# powerSwitch002.net
KiCad netlist of a schematic drawn in EAGLE
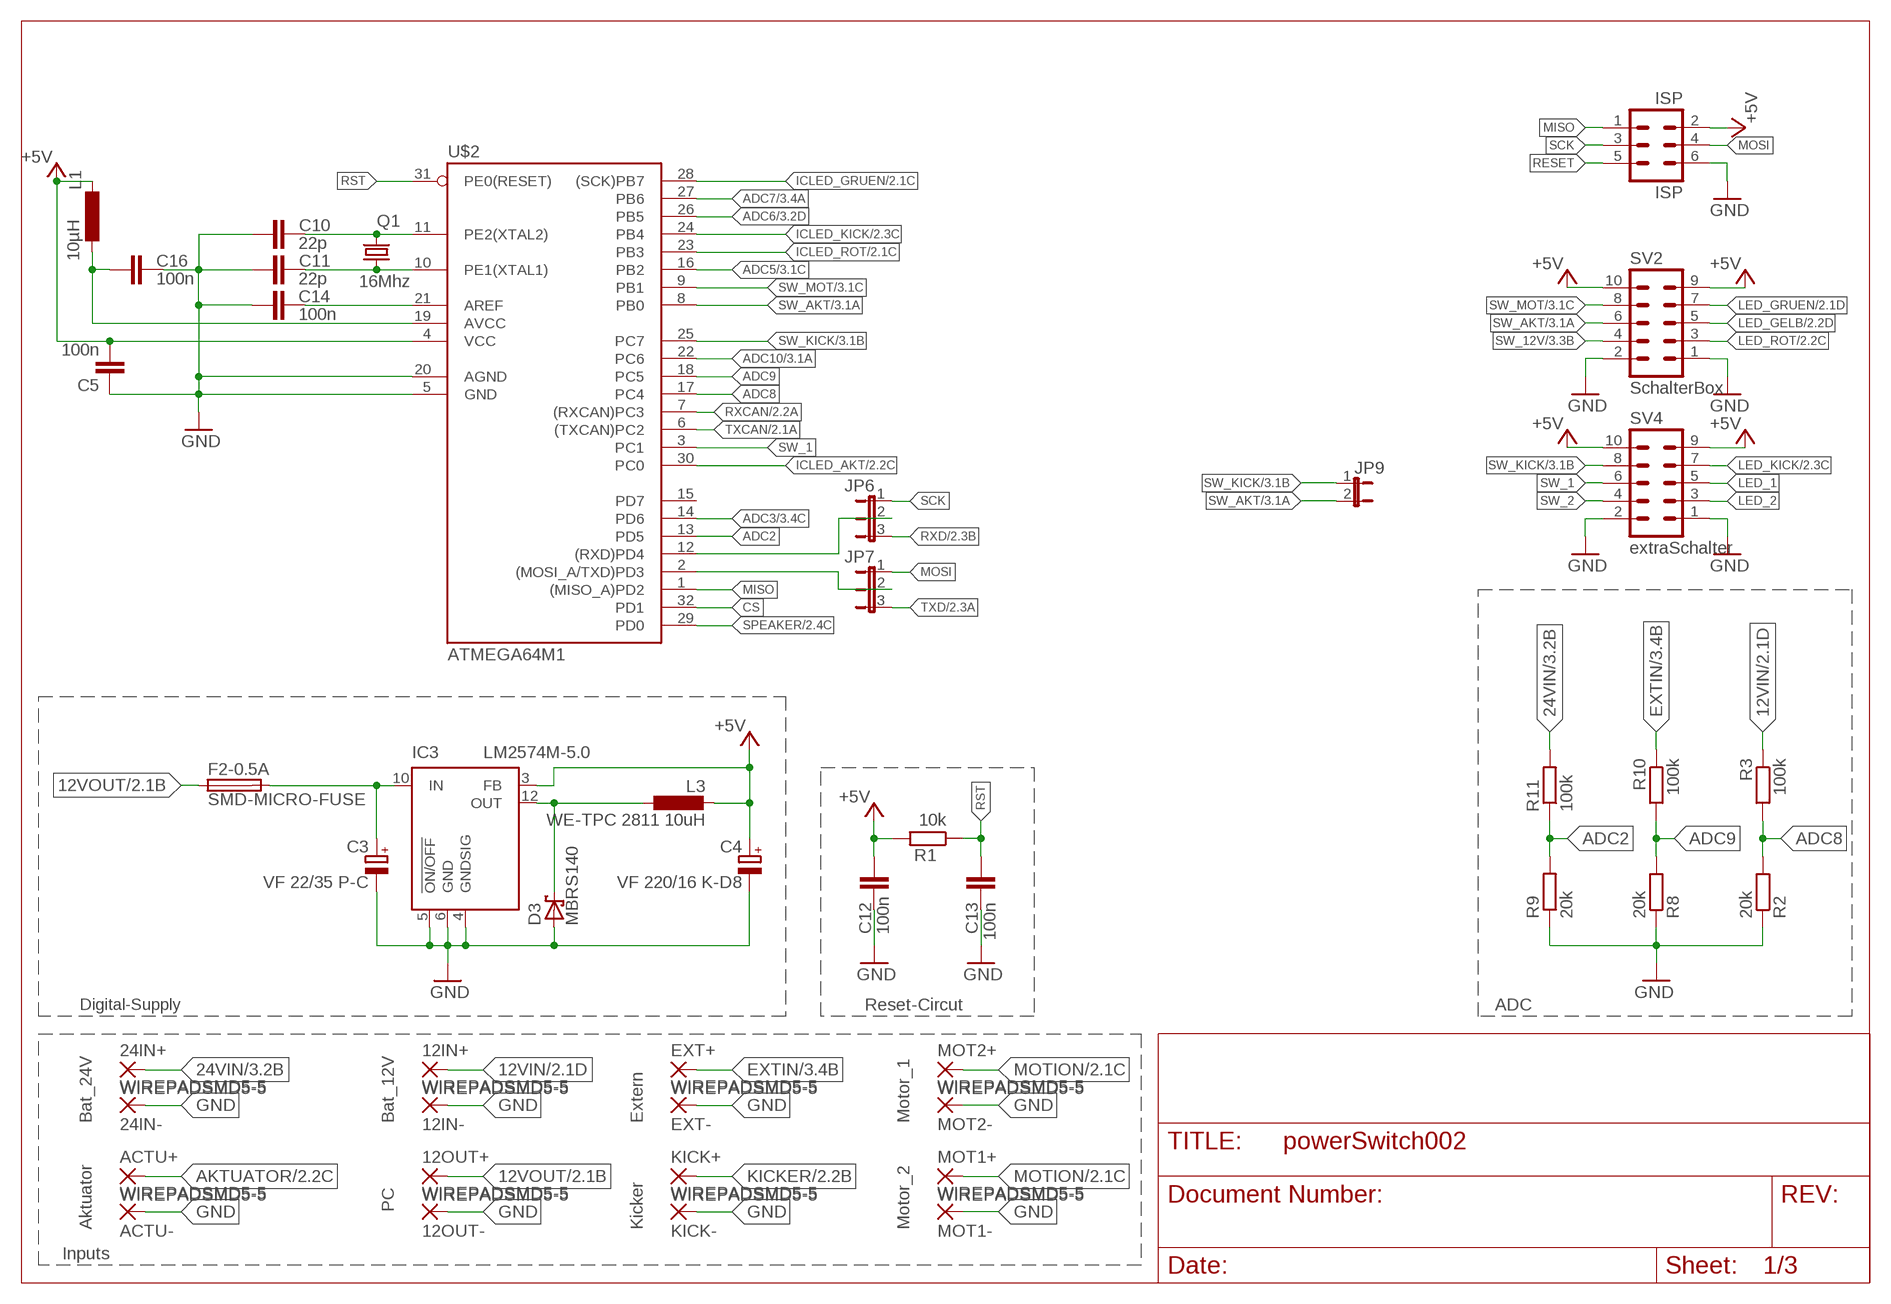
[diagram p0: schematic, sheet 1]
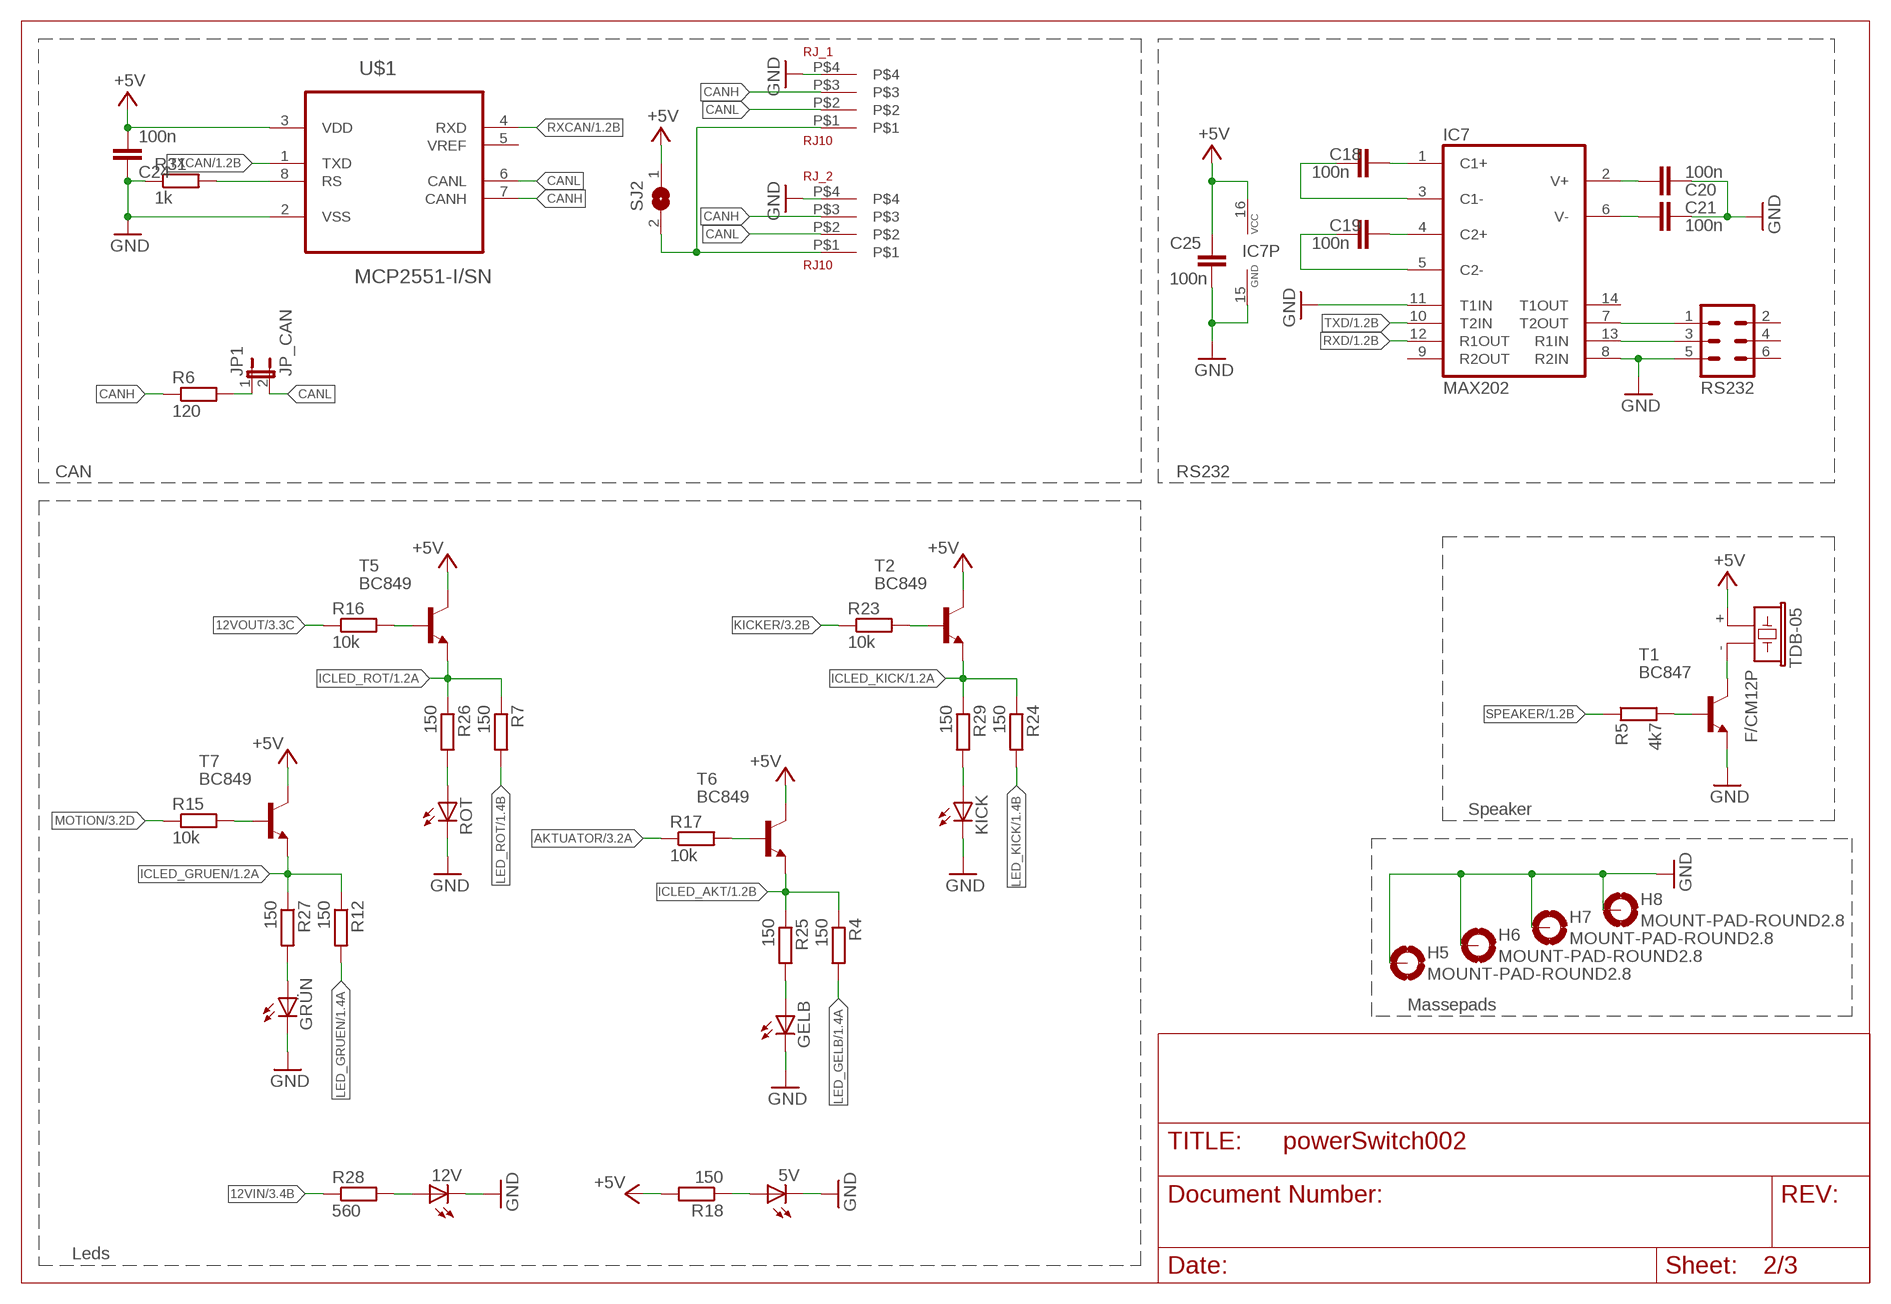
[diagram p1: schematic, sheet 2]
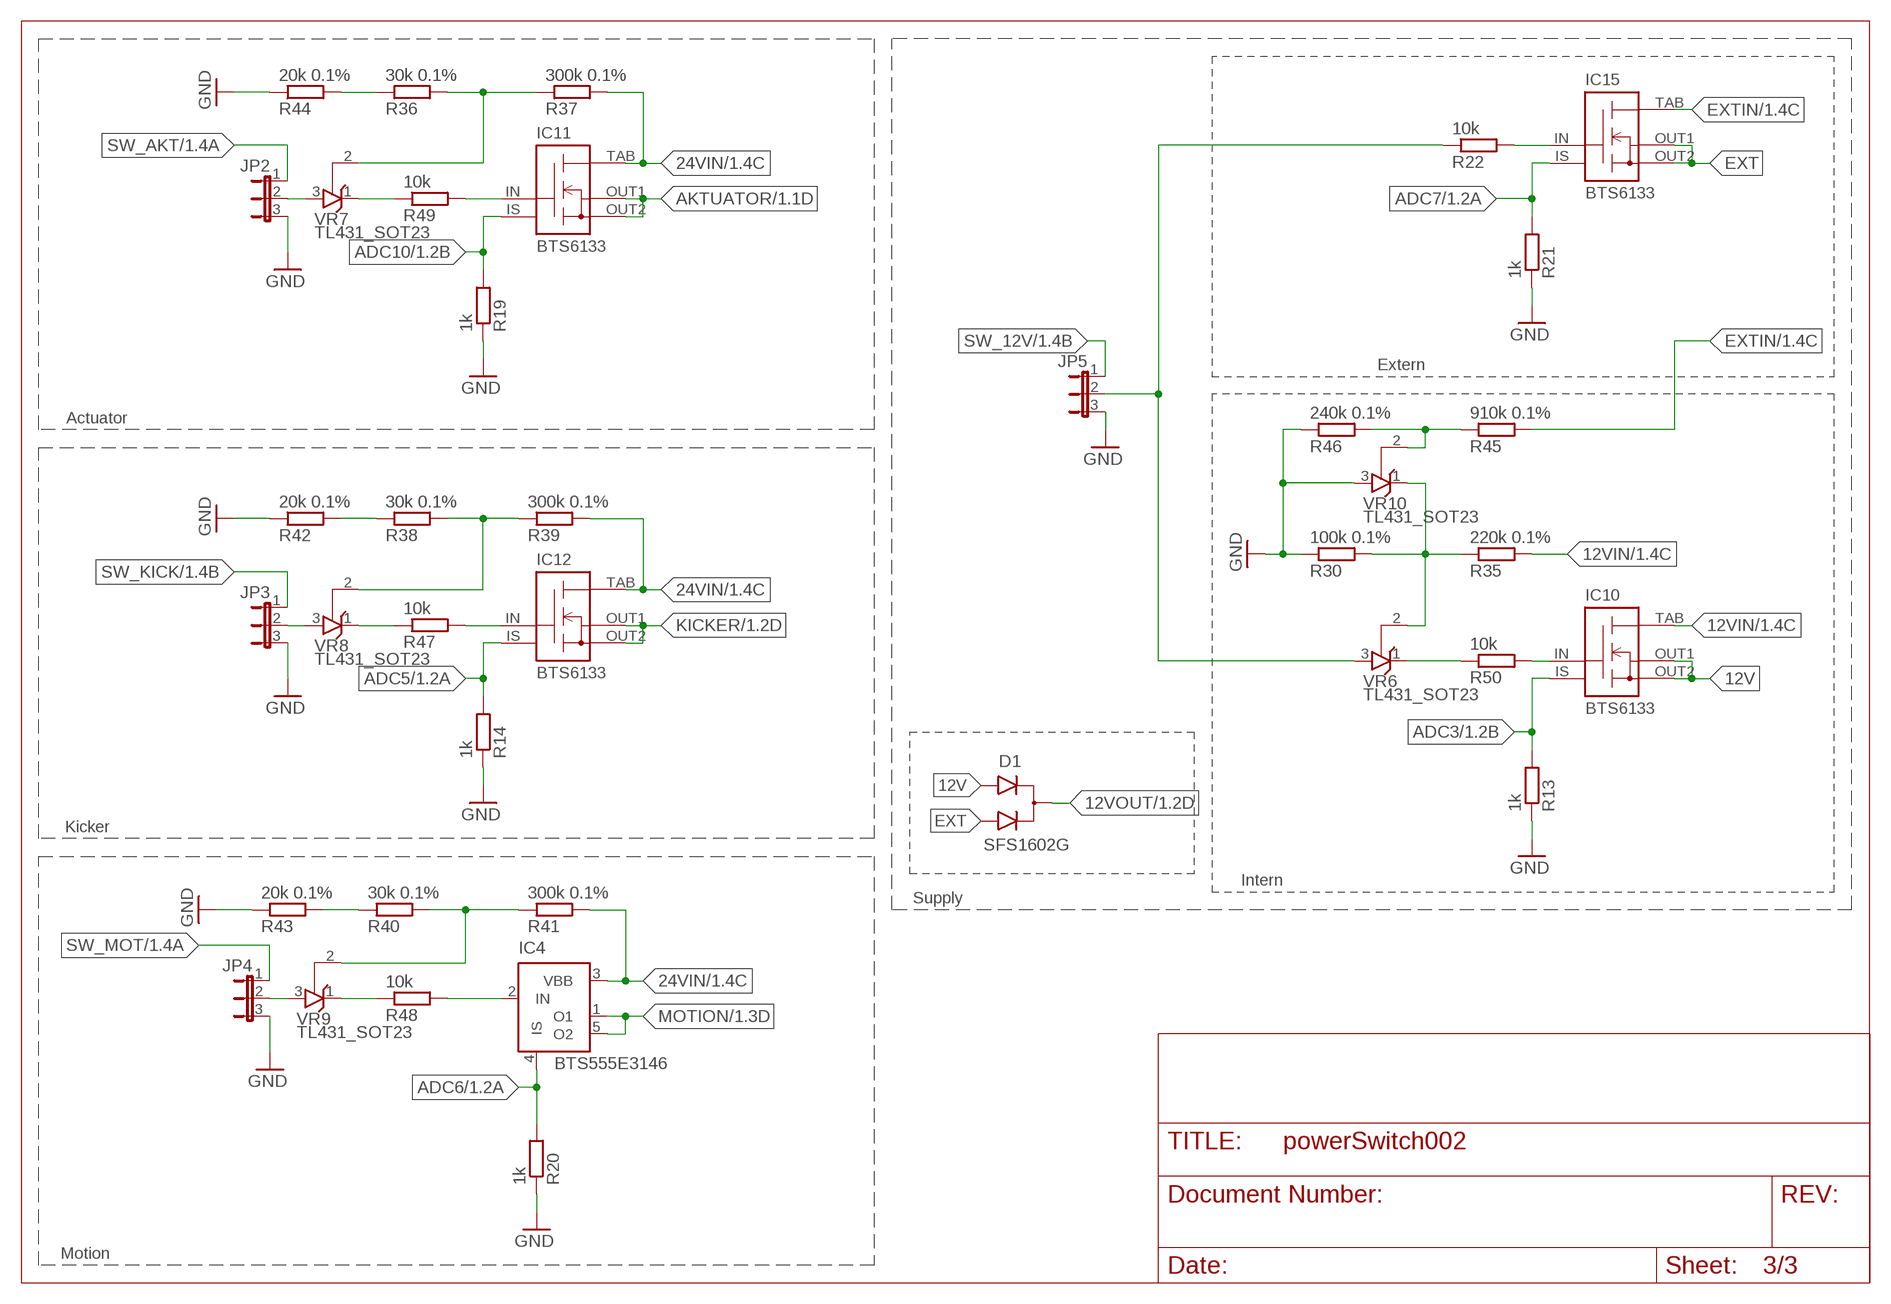
[diagram p2: schematic, sheet 3]

(export (version "E")
  (design (tool "Eeschema 10.0.6"))
  (components
    (comp (ref "12IN+")
      (value "WIREPADSMD5-5")
      (footprint "eagle-import:5-5")
      (libsource (lib "eagle-import") (part "WIREPADSMD5-5"))
    )
    (comp (ref "12IN-")
      (value "WIREPADSMD5-5")
      (footprint "eagle-import:5-5")
      (libsource (lib "eagle-import") (part "WIREPADSMD5-5"))
    )
    (comp (ref "12OUT+")
      (value "WIREPADSMD5-5")
      (footprint "eagle-import:5-5")
      (libsource (lib "eagle-import") (part "WIREPADSMD5-5"))
    )
    (comp (ref "12OUT-")
      (value "WIREPADSMD5-5")
      (footprint "eagle-import:5-5")
      (libsource (lib "eagle-import") (part "WIREPADSMD5-5"))
    )
    (comp (ref "24IN+")
      (value "WIREPADSMD5-5")
      (footprint "eagle-import:5-5")
      (libsource (lib "eagle-import") (part "WIREPADSMD5-5"))
    )
    (comp (ref "24IN-")
      (value "WIREPADSMD5-5")
      (footprint "eagle-import:5-5")
      (libsource (lib "eagle-import") (part "WIREPADSMD5-5"))
    )
    (comp (ref "ACTU+")
      (value "WIREPADSMD5-5")
      (footprint "eagle-import:5-5")
      (libsource (lib "eagle-import") (part "WIREPADSMD5-5"))
    )
    (comp (ref "ACTU-")
      (value "WIREPADSMD5-5")
      (footprint "eagle-import:5-5")
      (libsource (lib "eagle-import") (part "WIREPADSMD5-5"))
    )
    (comp (ref "C3")
      (value "VF 22/35 P-C")
      (footprint "eagle-import:PANASONIC_C")
      (libsource (lib "eagle-import") (part "CPOL-EUC"))
    )
    (comp (ref "C4")
      (value "VF 220/16 K-D8")
      (footprint "eagle-import:PANASONIC_D")
      (libsource (lib "eagle-import") (part "CPOL-EUD"))
    )
    (comp (ref "C5")
      (value "100n")
      (footprint "eagle-import:C0603K")
      (libsource (lib "eagle-import") (part "C-EUC0603K"))
    )
    (comp (ref "C10")
      (value "22p")
      (footprint "eagle-import:C0603K")
      (libsource (lib "eagle-import") (part "C-EUC0603K"))
    )
    (comp (ref "C11")
      (value "22p")
      (footprint "eagle-import:C0603K")
      (libsource (lib "eagle-import") (part "C-EUC0603K"))
    )
    (comp (ref "C12")
      (value "100n")
      (footprint "eagle-import:C0603K")
      (libsource (lib "eagle-import") (part "C-EUC0603K"))
    )
    (comp (ref "C13")
      (value "100n")
      (footprint "eagle-import:C0603K")
      (libsource (lib "eagle-import") (part "C-EUC0603K"))
    )
    (comp (ref "C14")
      (value "100n")
      (footprint "eagle-import:C0603K")
      (libsource (lib "eagle-import") (part "C-EUC0603K"))
    )
    (comp (ref "C16")
      (value "100n")
      (footprint "eagle-import:C0603K")
      (libsource (lib "eagle-import") (part "C-EUC0603K"))
    )
    (comp (ref "D3")
      (value "MBRS140")
      (footprint "eagle-import:SMB")
      (libsource (lib "eagle-import") (part "SCHOTTKY-DIODESMD"))
    )
    (comp (ref "EXT+")
      (value "WIREPADSMD5-5")
      (footprint "eagle-import:5-5")
      (libsource (lib "eagle-import") (part "WIREPADSMD5-5"))
    )
    (comp (ref "EXT-")
      (value "WIREPADSMD5-5")
      (footprint "eagle-import:5-5")
      (libsource (lib "eagle-import") (part "WIREPADSMD5-5"))
    )
    (comp (ref "F2-0.5A")
      (value "SMD-MICRO-FUSE")
      (footprint "eagle-import:SMD-6,1X2,6")
      (libsource (lib "eagle-import") (part "SMD-MICRO-FUSE"))
    )
    (comp (ref "IC3")
      (value "LM2574M-5.0")
      (footprint "eagle-import:SO14W")
      (libsource (lib "eagle-import") (part "LM2574?-M5.0"))
    )
    (comp (ref "ISP")
      (value "ISP")
      (footprint "eagle-import:ML6")
      (libsource (lib "eagle-import") (part "ML6"))
    )
    (comp (ref "JP6")
      (value "JP2E")
      (footprint "eagle-import:JP2")
      (libsource (lib "eagle-import") (part "JP2E"))
    )
    (comp (ref "JP7")
      (value "JP2E")
      (footprint "eagle-import:JP2")
      (libsource (lib "eagle-import") (part "JP2E"))
    )
    (comp (ref "JP9")
      (value "JP1E")
      (footprint "eagle-import:JP1")
      (libsource (lib "eagle-import") (part "JP1E"))
    )
    (comp (ref "KICK+")
      (value "WIREPADSMD5-5")
      (footprint "eagle-import:5-5")
      (libsource (lib "eagle-import") (part "WIREPADSMD5-5"))
    )
    (comp (ref "KICK-")
      (value "WIREPADSMD5-5")
      (footprint "eagle-import:5-5")
      (libsource (lib "eagle-import") (part "WIREPADSMD5-5"))
    )
    (comp (ref "L1")
      (value "10µH")
      (footprint "eagle-import:R0805")
      (libsource (lib "eagle-import") (part "L-EU-0805L0805"))
    )
    (comp (ref "L3")
      (value "WE-TPC 2811 10uH")
      (footprint "eagle-import:POWER-CHOKE_WE-TPC")
      (libsource (lib "eagle-import") (part "L-EUWE-TPC"))
    )
    (comp (ref "MOT1+")
      (value "WIREPADSMD5-5")
      (footprint "eagle-import:5-5")
      (libsource (lib "eagle-import") (part "WIREPADSMD5-5"))
    )
    (comp (ref "MOT1-")
      (value "WIREPADSMD5-5")
      (footprint "eagle-import:5-5")
      (libsource (lib "eagle-import") (part "WIREPADSMD5-5"))
    )
    (comp (ref "MOT2+")
      (value "WIREPADSMD5-5")
      (footprint "eagle-import:5-5")
      (libsource (lib "eagle-import") (part "WIREPADSMD5-5"))
    )
    (comp (ref "MOT2-")
      (value "WIREPADSMD5-5")
      (footprint "eagle-import:5-5")
      (libsource (lib "eagle-import") (part "WIREPADSMD5-5"))
    )
    (comp (ref "Q1")
      (value "16Mhz")
      (footprint "eagle-import:HC49U-V@1")
      (libsource (lib "eagle-import") (part "CRYTALHC49U-V"))
    )
    (comp (ref "R1")
      (value "10k")
      (footprint "eagle-import:R0805")
      (libsource (lib "eagle-import") (part "R-EU_R0805"))
    )
    (comp (ref "R2")
      (value "20k")
      (footprint "eagle-import:R0805")
      (libsource (lib "eagle-import") (part "R-EU_R0805"))
    )
    (comp (ref "R3")
      (value "100k")
      (footprint "eagle-import:R0805")
      (libsource (lib "eagle-import") (part "R-EU_R0805"))
    )
    (comp (ref "R8")
      (value "20k")
      (footprint "eagle-import:R0805")
      (libsource (lib "eagle-import") (part "R-EU_R0805"))
    )
    (comp (ref "R9")
      (value "20k")
      (footprint "eagle-import:R0805")
      (libsource (lib "eagle-import") (part "R-EU_R0805"))
    )
    (comp (ref "R10")
      (value "100k")
      (footprint "eagle-import:R0805")
      (libsource (lib "eagle-import") (part "R-EU_R0805"))
    )
    (comp (ref "R11")
      (value "100k")
      (footprint "eagle-import:R0805")
      (libsource (lib "eagle-import") (part "R-EU_R0805"))
    )
    (comp (ref "SV2")
      (value "SchalterBox")
      (footprint "eagle-import:ML10")
      (libsource (lib "eagle-import") (part "ML10"))
    )
    (comp (ref "SV4")
      (value "extraSchalter")
      (footprint "eagle-import:ML10")
      (libsource (lib "eagle-import") (part "ML10"))
    )
    (comp (ref "U$2")
      (value "ATMEGA64M1")
      (footprint "eagle-import:TQFP32-08")
      (libsource (lib "eagle-import") (part "ATMEGA64M1"))
    )
    (comp (ref "5V")
      (value "LEDCHIPLED_0805")
      (footprint "eagle-import:CHIPLED_0805")
      (libsource (lib "eagle-import") (part "LEDCHIPLED_0805"))
    )
    (comp (ref "12V")
      (value "LEDCHIPLED_0805")
      (footprint "eagle-import:CHIPLED_0805")
      (libsource (lib "eagle-import") (part "LEDCHIPLED_0805"))
    )
    (comp (ref "C18")
      (value "100n")
      (footprint "eagle-import:C0603K")
      (libsource (lib "eagle-import") (part "C-EUC0603K"))
    )
    (comp (ref "C19")
      (value "100n")
      (footprint "eagle-import:C0603K")
      (libsource (lib "eagle-import") (part "C-EUC0603K"))
    )
    (comp (ref "C20")
      (value "100n")
      (footprint "eagle-import:C0603K")
      (libsource (lib "eagle-import") (part "C-EUC0603K"))
    )
    (comp (ref "C21")
      (value "100n")
      (footprint "eagle-import:C0603K")
      (libsource (lib "eagle-import") (part "C-EUC0603K"))
    )
    (comp (ref "C24")
      (value "100n")
      (footprint "eagle-import:C0603")
      (libsource (lib "eagle-import") (part "C-EUC0603"))
    )
    (comp (ref "C25")
      (value "100n")
      (footprint "eagle-import:C0603K")
      (libsource (lib "eagle-import") (part "C-EUC0603K"))
    )
    (comp (ref "GELB")
      (value "LEDCHIPLED_0805")
      (footprint "eagle-import:CHIPLED_0805")
      (libsource (lib "eagle-import") (part "LEDCHIPLED_0805"))
    )
    (comp (ref "GRÜN")
      (value "LEDCHIPLED_0805")
      (footprint "eagle-import:CHIPLED_0805")
      (libsource (lib "eagle-import") (part "LEDCHIPLED_0805"))
    )
    (comp (ref "H5")
      (value "MOUNT-PAD-ROUND2.8")
      (footprint "eagle-import:2,8-PAD")
      (libsource (lib "eagle-import") (part "MOUNT-PAD-ROUND2.8"))
    )
    (comp (ref "H6")
      (value "MOUNT-PAD-ROUND2.8")
      (footprint "eagle-import:2,8-PAD")
      (libsource (lib "eagle-import") (part "MOUNT-PAD-ROUND2.8"))
    )
    (comp (ref "H7")
      (value "MOUNT-PAD-ROUND2.8")
      (footprint "eagle-import:2,8-PAD")
      (libsource (lib "eagle-import") (part "MOUNT-PAD-ROUND2.8"))
    )
    (comp (ref "H8")
      (value "MOUNT-PAD-ROUND2.8")
      (footprint "eagle-import:2,8-PAD")
      (libsource (lib "eagle-import") (part "MOUNT-PAD-ROUND2.8"))
    )
    (comp (ref "IC7")
      (value "MAX202")
      (footprint "eagle-import:SO16")
      (fields (field (name "MPN") "MAX3232CSE"))
      (libsource (lib "eagle-import") (part "MAX3232SEC"))
    )
    (comp (ref "JP1")
      (value "JP_CAN")
      (footprint "eagle-import:JP1")
      (libsource (lib "eagle-import") (part "JP1E"))
    )
    (comp (ref "KICK")
      (value "LEDCHIPLED_0805")
      (footprint "eagle-import:CHIPLED_0805")
      (libsource (lib "eagle-import") (part "LEDCHIPLED_0805"))
    )
    (comp (ref "R4")
      (value "150")
      (footprint "eagle-import:R0805")
      (libsource (lib "eagle-import") (part "R-EU_R0805"))
    )
    (comp (ref "R5")
      (value "4k7")
      (footprint "eagle-import:R0805")
      (libsource (lib "eagle-import") (part "R-EU_R0805"))
    )
    (comp (ref "R6")
      (value "120")
      (footprint "eagle-import:M0805")
      (libsource (lib "eagle-import") (part "R-EU_M0805"))
    )
    (comp (ref "R7")
      (value "150")
      (footprint "eagle-import:R0805")
      (libsource (lib "eagle-import") (part "R-EU_R0805"))
    )
    (comp (ref "R12")
      (value "150")
      (footprint "eagle-import:R0805")
      (libsource (lib "eagle-import") (part "R-EU_R0805"))
    )
    (comp (ref "R15")
      (value "10k")
      (footprint "eagle-import:R0805")
      (libsource (lib "eagle-import") (part "R-EU_R0805"))
    )
    (comp (ref "R16")
      (value "10k")
      (footprint "eagle-import:R0805")
      (libsource (lib "eagle-import") (part "R-EU_R0805"))
    )
    (comp (ref "R17")
      (value "10k")
      (footprint "eagle-import:R0805")
      (libsource (lib "eagle-import") (part "R-EU_R0805"))
    )
    (comp (ref "R18")
      (value "150")
      (footprint "eagle-import:R0805")
      (libsource (lib "eagle-import") (part "R-EU_R0805"))
    )
    (comp (ref "R23")
      (value "10k")
      (footprint "eagle-import:R0805")
      (libsource (lib "eagle-import") (part "R-EU_R0805"))
    )
    (comp (ref "R24")
      (value "150")
      (footprint "eagle-import:R0805")
      (libsource (lib "eagle-import") (part "R-EU_R0805"))
    )
    (comp (ref "R25")
      (value "150")
      (footprint "eagle-import:R0805")
      (libsource (lib "eagle-import") (part "R-EU_R0805"))
    )
    (comp (ref "R26")
      (value "150")
      (footprint "eagle-import:R0805")
      (libsource (lib "eagle-import") (part "R-EU_R0805"))
    )
    (comp (ref "R27")
      (value "150")
      (footprint "eagle-import:R0805")
      (libsource (lib "eagle-import") (part "R-EU_R0805"))
    )
    (comp (ref "R28")
      (value "560")
      (footprint "eagle-import:R0805")
      (libsource (lib "eagle-import") (part "R-EU_R0805"))
    )
    (comp (ref "R29")
      (value "150")
      (footprint "eagle-import:R0805")
      (libsource (lib "eagle-import") (part "R-EU_R0805"))
    )
    (comp (ref "R31")
      (value "1k")
      (footprint "eagle-import:R0805")
      (libsource (lib "eagle-import") (part "R-EU_R0805"))
    )
    (comp (ref "RJ_1")
      (value "RJ10")
      (footprint "eagle-import:RJ10")
      (libsource (lib "eagle-import") (part "RJ10"))
    )
    (comp (ref "RJ_2")
      (value "RJ10")
      (footprint "eagle-import:RJ10")
      (libsource (lib "eagle-import") (part "RJ10"))
    )
    (comp (ref "ROT")
      (value "LEDCHIPLED_0805")
      (footprint "eagle-import:CHIPLED_0805")
      (libsource (lib "eagle-import") (part "LEDCHIPLED_0805"))
    )
    (comp (ref "RS232")
      (value "ML6")
      (footprint "eagle-import:ML6")
      (libsource (lib "eagle-import") (part "ML6"))
    )
    (comp (ref "SJ2") (value "SJ") (footprint "eagle-import:SJ") (libsource (lib "eagle-import") (part "SJ")))
    (comp (ref "T1")
      (value "BC847")
      (footprint "eagle-import:SOT23")
      (libsource (lib "eagle-import") (part "BC847"))
    )
    (comp (ref "T2")
      (value "BC849")
      (footprint "eagle-import:SOT23")
      (libsource (lib "eagle-import") (part "BC849"))
    )
    (comp (ref "T5")
      (value "BC849")
      (footprint "eagle-import:SOT23")
      (libsource (lib "eagle-import") (part "BC849"))
    )
    (comp (ref "T6")
      (value "BC849")
      (footprint "eagle-import:SOT23")
      (libsource (lib "eagle-import") (part "BC849"))
    )
    (comp (ref "T7")
      (value "BC849")
      (footprint "eagle-import:SOT23")
      (libsource (lib "eagle-import") (part "BC849"))
    )
    (comp (ref "TDB-05")
      (value "F/CM12P")
      (footprint "eagle-import:F_CM12P")
      (libsource (lib "eagle-import") (part "F/CM12P"))
    )
    (comp (ref "U$1")
      (value "MCP2551-I/SN")
      (footprint "eagle-import:SOIC127P600X175-8N")
      (libsource (lib "eagle-import") (part "MCP2551-I/SN"))
    )
    (comp (ref "D1")
      (value "SFS1602G")
      (footprint "eagle-import:D2PAK")
      (libsource (lib "eagle-import") (part "SFS160G"))
    )
    (comp (ref "IC4")
      (value "BTS555E3146")
      (footprint "eagle-import:TO220-52")
      (libsource (lib "eagle-import") (part "BTS555E3146"))
    )
    (comp (ref "IC10")
      (value "BTS6133")
      (footprint "eagle-import:TO252-51")
      (libsource (lib "eagle-import") (part "BTS6133"))
    )
    (comp (ref "IC11")
      (value "BTS6133")
      (footprint "eagle-import:TO252-51")
      (libsource (lib "eagle-import") (part "BTS6133"))
    )
    (comp (ref "IC12")
      (value "BTS6133")
      (footprint "eagle-import:TO252-51")
      (libsource (lib "eagle-import") (part "BTS6133"))
    )
    (comp (ref "IC15")
      (value "BTS6133")
      (footprint "eagle-import:TO252-51")
      (libsource (lib "eagle-import") (part "BTS6133"))
    )
    (comp (ref "JP2")
      (value "JP2E")
      (footprint "eagle-import:JP2")
      (libsource (lib "eagle-import") (part "JP2E"))
    )
    (comp (ref "JP3")
      (value "JP2E")
      (footprint "eagle-import:JP2")
      (libsource (lib "eagle-import") (part "JP2E"))
    )
    (comp (ref "JP4")
      (value "JP2E")
      (footprint "eagle-import:JP2")
      (libsource (lib "eagle-import") (part "JP2E"))
    )
    (comp (ref "JP5")
      (value "JP2E")
      (footprint "eagle-import:JP2")
      (libsource (lib "eagle-import") (part "JP2E"))
    )
    (comp (ref "R13")
      (value "1k")
      (footprint "eagle-import:R0805")
      (libsource (lib "eagle-import") (part "R-EU_R0805"))
    )
    (comp (ref "R14")
      (value "1k")
      (footprint "eagle-import:R0805")
      (libsource (lib "eagle-import") (part "R-EU_R0805"))
    )
    (comp (ref "R19")
      (value "1k")
      (footprint "eagle-import:R0805")
      (libsource (lib "eagle-import") (part "R-EU_R0805"))
    )
    (comp (ref "R20")
      (value "1k")
      (footprint "eagle-import:R0805")
      (libsource (lib "eagle-import") (part "R-EU_R0805"))
    )
    (comp (ref "R21")
      (value "1k")
      (footprint "eagle-import:R0805")
      (libsource (lib "eagle-import") (part "R-EU_R0805"))
    )
    (comp (ref "R22")
      (value "10k")
      (footprint "eagle-import:R0805")
      (libsource (lib "eagle-import") (part "R-EU_R0805"))
    )
    (comp (ref "R30")
      (value "100k 0.1%")
      (footprint "eagle-import:R0805")
      (libsource (lib "eagle-import") (part "R-EU_R0805"))
    )
    (comp (ref "R35")
      (value "220k 0.1%")
      (footprint "eagle-import:R0805")
      (libsource (lib "eagle-import") (part "R-EU_R0805"))
    )
    (comp (ref "R36")
      (value "30k 0.1%")
      (footprint "eagle-import:R0805")
      (libsource (lib "eagle-import") (part "R-EU_R0805"))
    )
    (comp (ref "R37")
      (value "300k 0.1%")
      (footprint "eagle-import:R0805")
      (libsource (lib "eagle-import") (part "R-EU_R0805"))
    )
    (comp (ref "R38")
      (value "30k 0.1%")
      (footprint "eagle-import:R0805")
      (libsource (lib "eagle-import") (part "R-EU_R0805"))
    )
    (comp (ref "R39")
      (value "300k 0.1%")
      (footprint "eagle-import:R0805")
      (libsource (lib "eagle-import") (part "R-EU_R0805"))
    )
    (comp (ref "R40")
      (value "30k 0.1%")
      (footprint "eagle-import:R0805")
      (libsource (lib "eagle-import") (part "R-EU_R0805"))
    )
    (comp (ref "R41")
      (value "300k 0.1%")
      (footprint "eagle-import:R0805")
      (libsource (lib "eagle-import") (part "R-EU_R0805"))
    )
    (comp (ref "R42")
      (value "20k 0.1%")
      (footprint "eagle-import:R0805")
      (libsource (lib "eagle-import") (part "R-EU_R0805"))
    )
    (comp (ref "R43")
      (value "20k 0.1%")
      (footprint "eagle-import:R0805")
      (libsource (lib "eagle-import") (part "R-EU_R0805"))
    )
    (comp (ref "R44")
      (value "20k 0.1%")
      (footprint "eagle-import:R0805")
      (libsource (lib "eagle-import") (part "R-EU_R0805"))
    )
    (comp (ref "R45")
      (value "910k 0.1%")
      (footprint "eagle-import:R0805")
      (libsource (lib "eagle-import") (part "R-EU_R0805"))
    )
    (comp (ref "R46")
      (value "240k 0.1%")
      (footprint "eagle-import:R0805")
      (libsource (lib "eagle-import") (part "R-EU_R0805"))
    )
    (comp (ref "R47")
      (value "10k")
      (footprint "eagle-import:R0805")
      (libsource (lib "eagle-import") (part "R-EU_R0805"))
    )
    (comp (ref "R48")
      (value "10k")
      (footprint "eagle-import:R0805")
      (libsource (lib "eagle-import") (part "R-EU_R0805"))
    )
    (comp (ref "R49")
      (value "10k")
      (footprint "eagle-import:R0805")
      (libsource (lib "eagle-import") (part "R-EU_R0805"))
    )
    (comp (ref "R50")
      (value "10k")
      (footprint "eagle-import:R0805")
      (libsource (lib "eagle-import") (part "R-EU_R0805"))
    )
    (comp (ref "VR6")
      (value "TL431_SOT23")
      (footprint "eagle-import:SOT23")
      (libsource (lib "eagle-import") (part "TL431_SOT23"))
    )
    (comp (ref "VR7")
      (value "TL431_SOT23")
      (footprint "eagle-import:SOT23")
      (libsource (lib "eagle-import") (part "TL431_SOT23"))
    )
    (comp (ref "VR8")
      (value "TL431_SOT23")
      (footprint "eagle-import:SOT23")
      (libsource (lib "eagle-import") (part "TL431_SOT23"))
    )
    (comp (ref "VR9")
      (value "TL431_SOT23")
      (footprint "eagle-import:SOT23")
      (libsource (lib "eagle-import") (part "TL431_SOT23"))
    )
    (comp (ref "VR10")
      (value "TL431_SOT23")
      (footprint "eagle-import:SOT23")
      (libsource (lib "eagle-import") (part "TL431_SOT23"))
    )
  )
  (nets
    (net (code "1") (name "+5V") (class "Default")
      (node (ref "C12") (pin "2") (pinfunction "2_2") (pintype "passive"))
      (node (ref "C24") (pin "2") (pinfunction "2_2") (pintype "passive"))
      (node (ref "C25") (pin "1") (pinfunction "1_1") (pintype "passive"))
      (node (ref "C4") (pin "+") (pinfunction "+_+") (pintype "passive"))
      (node (ref "C5") (pin "2") (pinfunction "2_2") (pintype "passive"))
      (node (ref "IC3") (pin "3") (pinfunction "FB_3") (pintype "input"))
      (node (ref "IC7") (pin "16") (pinfunction "VCC_16") (pintype "power_in"))
      (node (ref "ISP") (pin "2") (pinfunction "2_2") (pintype "passive"))
      (node (ref "L1") (pin "2") (pinfunction "2_2") (pintype "passive"))
      (node (ref "L3") (pin "2") (pinfunction "2_2") (pintype "passive"))
      (node (ref "R1") (pin "2") (pinfunction "2_2") (pintype "passive"))
      (node (ref "R18") (pin "2") (pinfunction "2_2") (pintype "passive"))
      (node (ref "SJ2") (pin "1") (pinfunction "1_1") (pintype "passive"))
      (node (ref "SV2") (pin "10") (pinfunction "10_10") (pintype "passive"))
      (node (ref "SV2") (pin "9") (pinfunction "9_9") (pintype "passive"))
      (node (ref "SV4") (pin "10") (pinfunction "10_10") (pintype "passive"))
      (node (ref "SV4") (pin "9") (pinfunction "9_9") (pintype "passive"))
      (node (ref "T2") (pin "3") (pinfunction "C_3") (pintype "passive"))
      (node (ref "T5") (pin "3") (pinfunction "C_3") (pintype "passive"))
      (node (ref "T6") (pin "3") (pinfunction "C_3") (pintype "passive"))
      (node (ref "T7") (pin "3") (pinfunction "C_3") (pintype "passive"))
      (node (ref "TDB-05") (pin "+") (pinfunction "1_+") (pintype "passive"))
      (node (ref "U$1") (pin "3") (pinfunction "VDD_3") (pintype "power_in"))
      (node (ref "U$2") (pin "4") (pinfunction "VCC_4") (pintype "bidirectional"))
    )
    (net (code "2") (name "12V") (class "Default")
      (node (ref "D1") (pin "P$1") (pinfunction "P$1_P$1") (pintype "bidirectional"))
      (node (ref "IC10") (pin "OUT1") (pinfunction "OUT_OUT1") (pintype "passive"))
      (node (ref "IC10") (pin "OUT2") (pinfunction "OUT_OUT2") (pintype "passive"))
    )
    (net (code "3") (name "12VIN") (class "Default")
      (node (ref "12IN+") (pin "P$1") (pinfunction "P_P$1") (pintype "passive"))
      (node (ref "IC10") (pin "TAB") (pinfunction "VBB_TAB") (pintype "power_in"))
      (node (ref "R28") (pin "1") (pinfunction "1_1") (pintype "passive"))
      (node (ref "R3") (pin "1") (pinfunction "1_1") (pintype "passive"))
      (node (ref "R35") (pin "2") (pinfunction "2_2") (pintype "passive"))
    )
    (net (code "4") (name "12VOUT") (class "Default")
      (node (ref "12OUT+") (pin "P$1") (pinfunction "P_P$1") (pintype "passive"))
      (node (ref "D1") (pin "P$3") (pinfunction "P$3_P$3") (pintype "bidirectional"))
      (node (ref "F2-0.5A") (pin "1") (pinfunction "1_1") (pintype "passive"))
      (node (ref "R16") (pin "1") (pinfunction "1_1") (pintype "passive"))
    )
    (net (code "5") (name "24VIN") (class "Default")
      (node (ref "24IN+") (pin "P$1") (pinfunction "P_P$1") (pintype "passive"))
      (node (ref "IC11") (pin "TAB") (pinfunction "VBB_TAB") (pintype "power_in"))
      (node (ref "IC12") (pin "TAB") (pinfunction "VBB_TAB") (pintype "power_in"))
      (node (ref "IC4") (pin "3") (pinfunction "VBB_3") (pintype "passive"))
      (node (ref "R11") (pin "2") (pinfunction "2_2") (pintype "passive"))
      (node (ref "R37") (pin "2") (pinfunction "2_2") (pintype "passive"))
      (node (ref "R39") (pin "2") (pinfunction "2_2") (pintype "passive"))
      (node (ref "R41") (pin "2") (pinfunction "2_2") (pintype "passive"))
    )
    (net (code "6") (name "ADC2") (class "Default")
      (node (ref "R11") (pin "1") (pinfunction "1_1") (pintype "passive"))
      (node (ref "R9") (pin "2") (pinfunction "2_2") (pintype "passive"))
      (node (ref "U$2") (pin "13") (pinfunction "PD5_13") (pintype "bidirectional"))
    )
    (net (code "7") (name "ADC3") (class "Default")
      (node (ref "IC10") (pin "IS") (pinfunction "IS_IS") (pintype "passive"))
      (node (ref "R13") (pin "2") (pinfunction "2_2") (pintype "passive"))
      (node (ref "U$2") (pin "14") (pinfunction "PD6_14") (pintype "bidirectional"))
    )
    (net (code "8") (name "ADC5") (class "Default")
      (node (ref "IC12") (pin "IS") (pinfunction "IS_IS") (pintype "passive"))
      (node (ref "R14") (pin "2") (pinfunction "2_2") (pintype "passive"))
      (node (ref "U$2") (pin "16") (pinfunction "PB2_16") (pintype "bidirectional"))
    )
    (net (code "9") (name "ADC6") (class "Default")
      (node (ref "IC4") (pin "4") (pinfunction "IS_4") (pintype "passive"))
      (node (ref "R20") (pin "2") (pinfunction "2_2") (pintype "passive"))
      (node (ref "U$2") (pin "26") (pinfunction "PB5_26") (pintype "bidirectional"))
    )
    (net (code "10") (name "ADC7") (class "Default")
      (node (ref "IC15") (pin "IS") (pinfunction "IS_IS") (pintype "passive"))
      (node (ref "R21") (pin "2") (pinfunction "2_2") (pintype "passive"))
      (node (ref "U$2") (pin "27") (pinfunction "PB6_27") (pintype "bidirectional"))
    )
    (net (code "11") (name "ADC8") (class "Default")
      (node (ref "R2") (pin "2") (pinfunction "2_2") (pintype "passive"))
      (node (ref "R3") (pin "2") (pinfunction "2_2") (pintype "passive"))
      (node (ref "U$2") (pin "17") (pinfunction "PC4_17") (pintype "bidirectional"))
    )
    (net (code "12") (name "ADC9") (class "Default")
      (node (ref "R10") (pin "2") (pinfunction "2_2") (pintype "passive"))
      (node (ref "R8") (pin "2") (pinfunction "2_2") (pintype "passive"))
      (node (ref "U$2") (pin "18") (pinfunction "PC5_18") (pintype "bidirectional"))
    )
    (net (code "13") (name "ADC10") (class "Default")
      (node (ref "IC11") (pin "IS") (pinfunction "IS_IS") (pintype "passive"))
      (node (ref "R19") (pin "2") (pinfunction "2_2") (pintype "passive"))
      (node (ref "U$2") (pin "22") (pinfunction "PC6_22") (pintype "bidirectional"))
    )
    (net (code "14") (name "AKTUATOR") (class "Default")
      (node (ref "ACTU+") (pin "P$1") (pinfunction "P_P$1") (pintype "passive"))
      (node (ref "IC11") (pin "OUT1") (pinfunction "OUT_OUT1") (pintype "passive"))
      (node (ref "IC11") (pin "OUT2") (pinfunction "OUT_OUT2") (pintype "passive"))
      (node (ref "R17") (pin "1") (pinfunction "1_1") (pintype "passive"))
    )
    (net (code "15") (name "CANH") (class "Default")
      (node (ref "R6") (pin "1") (pinfunction "1_1") (pintype "passive"))
      (node (ref "RJ_1") (pin "P$3") (pinfunction "P$3_P$3") (pintype "bidirectional"))
      (node (ref "RJ_2") (pin "P$3") (pinfunction "P$3_P$3") (pintype "bidirectional"))
      (node (ref "U$1") (pin "7") (pinfunction "CANH_7") (pintype "bidirectional"))
    )
    (net (code "16") (name "CANL") (class "Default")
      (node (ref "JP1") (pin "2") (pinfunction "2_2") (pintype "passive"))
      (node (ref "RJ_1") (pin "P$2") (pinfunction "P$2_P$2") (pintype "bidirectional"))
      (node (ref "RJ_2") (pin "P$2") (pinfunction "P$2_P$2") (pintype "bidirectional"))
      (node (ref "U$1") (pin "6") (pinfunction "CANL_6") (pintype "bidirectional"))
    )
    (net (code "17") (name "CS") (class "Default")
      (node (ref "U$2") (pin "32") (pinfunction "PD1_32") (pintype "bidirectional"))
    )
    (net (code "18") (name "EXT") (class "Default")
      (node (ref "D1") (pin "P$2") (pinfunction "P$2_P$2") (pintype "bidirectional"))
      (node (ref "IC15") (pin "OUT1") (pinfunction "OUT_OUT1") (pintype "passive"))
      (node (ref "IC15") (pin "OUT2") (pinfunction "OUT_OUT2") (pintype "passive"))
    )
    (net (code "19") (name "EXTIN") (class "Default")
      (node (ref "EXT+") (pin "P$1") (pinfunction "P_P$1") (pintype "passive"))
      (node (ref "IC15") (pin "TAB") (pinfunction "VBB_TAB") (pintype "power_in"))
      (node (ref "R10") (pin "1") (pinfunction "1_1") (pintype "passive"))
      (node (ref "R45") (pin "2") (pinfunction "2_2") (pintype "passive"))
    )
    (net (code "20") (name "GND") (class "Default")
      (node (ref "12IN-") (pin "P$1") (pinfunction "P_P$1") (pintype "passive"))
      (node (ref "12OUT-") (pin "P$1") (pinfunction "P_P$1") (pintype "passive"))
      (node (ref "12V") (pin "C") (pinfunction "C_C") (pintype "passive"))
      (node (ref "24IN-") (pin "P$1") (pinfunction "P_P$1") (pintype "passive"))
      (node (ref "5V") (pin "C") (pinfunction "C_C") (pintype "passive"))
      (node (ref "ACTU-") (pin "P$1") (pinfunction "P_P$1") (pintype "passive"))
      (node (ref "C10") (pin "1") (pinfunction "1_1") (pintype "passive"))
      (node (ref "C11") (pin "1") (pinfunction "1_1") (pintype "passive"))
      (node (ref "C12") (pin "1") (pinfunction "1_1") (pintype "passive"))
      (node (ref "C13") (pin "1") (pinfunction "1_1") (pintype "passive"))
      (node (ref "C14") (pin "1") (pinfunction "1_1") (pintype "passive"))
      (node (ref "C16") (pin "2") (pinfunction "2_2") (pintype "passive"))
      (node (ref "C20") (pin "2") (pinfunction "2_2") (pintype "passive"))
      (node (ref "C21") (pin "2") (pinfunction "2_2") (pintype "passive"))
      (node (ref "C24") (pin "1") (pinfunction "1_1") (pintype "passive"))
      (node (ref "C25") (pin "2") (pinfunction "2_2") (pintype "passive"))
      (node (ref "C3") (pin "-") (pinfunction "-_-") (pintype "passive"))
      (node (ref "C4") (pin "-") (pinfunction "-_-") (pintype "passive"))
      (node (ref "C5") (pin "1") (pinfunction "1_1") (pintype "passive"))
      (node (ref "D3") (pin "A") (pinfunction "A_A") (pintype "passive"))
      (node (ref "EXT-") (pin "P$1") (pinfunction "P_P$1") (pintype "passive"))
      (node (ref "GELB") (pin "C") (pinfunction "C_C") (pintype "passive"))
      (node (ref "GRÜN") (pin "C") (pinfunction "C_C") (pintype "passive"))
      (node (ref "H5") (pin "B2,8") (pinfunction "MOUNT_B2,8") (pintype "passive"))
      (node (ref "H6") (pin "B2,8") (pinfunction "MOUNT_B2,8") (pintype "passive"))
      (node (ref "H7") (pin "B2,8") (pinfunction "MOUNT_B2,8") (pintype "passive"))
      (node (ref "H8") (pin "B2,8") (pinfunction "MOUNT_B2,8") (pintype "passive"))
      (node (ref "IC3") (pin "4") (pinfunction "GNDSIG_4") (pintype "input"))
      (node (ref "IC3") (pin "5") (pinfunction "~{ON/OFF}_5") (pintype "input"))
      (node (ref "IC3") (pin "6") (pinfunction "GND_6") (pintype "power_in"))
      (node (ref "IC7") (pin "11") (pinfunction "T1IN_11") (pintype "input"))
      (node (ref "IC7") (pin "15") (pinfunction "GND_15") (pintype "power_in"))
      (node (ref "IC7") (pin "8") (pinfunction "R2IN_8") (pintype "input"))
      (node (ref "ISP") (pin "6") (pinfunction "6_6") (pintype "passive"))
      (node (ref "JP2") (pin "3") (pinfunction "3_3") (pintype "passive"))
      (node (ref "JP3") (pin "3") (pinfunction "3_3") (pintype "passive"))
      (node (ref "JP4") (pin "3") (pinfunction "3_3") (pintype "passive"))
      (node (ref "JP5") (pin "3") (pinfunction "3_3") (pintype "passive"))
      (node (ref "KICK") (pin "C") (pinfunction "C_C") (pintype "passive"))
      (node (ref "KICK-") (pin "P$1") (pinfunction "P_P$1") (pintype "passive"))
      (node (ref "MOT1-") (pin "P$1") (pinfunction "P_P$1") (pintype "passive"))
      (node (ref "MOT2-") (pin "P$1") (pinfunction "P_P$1") (pintype "passive"))
      (node (ref "R13") (pin "1") (pinfunction "1_1") (pintype "passive"))
      (node (ref "R14") (pin "1") (pinfunction "1_1") (pintype "passive"))
      (node (ref "R19") (pin "1") (pinfunction "1_1") (pintype "passive"))
      (node (ref "R2") (pin "1") (pinfunction "1_1") (pintype "passive"))
      (node (ref "R20") (pin "1") (pinfunction "1_1") (pintype "passive"))
      (node (ref "R21") (pin "1") (pinfunction "1_1") (pintype "passive"))
      (node (ref "R30") (pin "1") (pinfunction "1_1") (pintype "passive"))
      (node (ref "R31") (pin "1") (pinfunction "1_1") (pintype "passive"))
      (node (ref "R42") (pin "1") (pinfunction "1_1") (pintype "passive"))
      (node (ref "R43") (pin "1") (pinfunction "1_1") (pintype "passive"))
      (node (ref "R44") (pin "1") (pinfunction "1_1") (pintype "passive"))
      (node (ref "R46") (pin "1") (pinfunction "1_1") (pintype "passive"))
      (node (ref "R8") (pin "1") (pinfunction "1_1") (pintype "passive"))
      (node (ref "R9") (pin "1") (pinfunction "1_1") (pintype "passive"))
      (node (ref "RJ_1") (pin "P$4") (pinfunction "P$4_P$4") (pintype "bidirectional"))
      (node (ref "RJ_2") (pin "P$4") (pinfunction "P$4_P$4") (pintype "bidirectional"))
      (node (ref "ROT") (pin "C") (pinfunction "C_C") (pintype "passive"))
      (node (ref "RS232") (pin "5") (pinfunction "5_5") (pintype "passive"))
      (node (ref "SV2") (pin "1") (pinfunction "1_1") (pintype "passive"))
      (node (ref "SV2") (pin "2") (pinfunction "2_2") (pintype "passive"))
      (node (ref "SV4") (pin "1") (pinfunction "1_1") (pintype "passive"))
      (node (ref "SV4") (pin "2") (pinfunction "2_2") (pintype "passive"))
      (node (ref "T1") (pin "2") (pinfunction "E_2") (pintype "passive"))
      (node (ref "U$1") (pin "2") (pinfunction "VSS_2") (pintype "passive"))
      (node (ref "U$2") (pin "20") (pinfunction "AGND_20") (pintype "power_in"))
      (node (ref "U$2") (pin "5") (pinfunction "GND_5") (pintype "power_in"))
      (node (ref "VR10") (pin "3") (pinfunction "A_3") (pintype "passive"))
    )
    (net (code "21") (name "ICLED_AKT") (class "Default")
      (node (ref "R25") (pin "1") (pinfunction "1_1") (pintype "passive"))
      (node (ref "R4") (pin "1") (pinfunction "1_1") (pintype "passive"))
      (node (ref "T6") (pin "2") (pinfunction "E_2") (pintype "passive"))
      (node (ref "U$2") (pin "30") (pinfunction "PC0_30") (pintype "bidirectional"))
    )
    (net (code "22") (name "ICLED_GRUEN") (class "Default")
      (node (ref "R12") (pin "1") (pinfunction "1_1") (pintype "passive"))
      (node (ref "R27") (pin "1") (pinfunction "1_1") (pintype "passive"))
      (node (ref "T7") (pin "2") (pinfunction "E_2") (pintype "passive"))
      (node (ref "U$2") (pin "28") (pinfunction "(SCK)PB7_28") (pintype "bidirectional"))
    )
    (net (code "23") (name "ICLED_KICK") (class "Default")
      (node (ref "R24") (pin "1") (pinfunction "1_1") (pintype "passive"))
      (node (ref "R29") (pin "1") (pinfunction "1_1") (pintype "passive"))
      (node (ref "T2") (pin "2") (pinfunction "E_2") (pintype "passive"))
      (node (ref "U$2") (pin "24") (pinfunction "PB4_24") (pintype "bidirectional"))
    )
    (net (code "24") (name "ICLED_ROT") (class "Default")
      (node (ref "R26") (pin "1") (pinfunction "1_1") (pintype "passive"))
      (node (ref "R7") (pin "1") (pinfunction "1_1") (pintype "passive"))
      (node (ref "T5") (pin "2") (pinfunction "E_2") (pintype "passive"))
      (node (ref "U$2") (pin "23") (pinfunction "PB3_23") (pintype "bidirectional"))
    )
    (net (code "25") (name "KICKER") (class "Default")
      (node (ref "IC12") (pin "OUT1") (pinfunction "OUT_OUT1") (pintype "passive"))
      (node (ref "IC12") (pin "OUT2") (pinfunction "OUT_OUT2") (pintype "passive"))
      (node (ref "KICK+") (pin "P$1") (pinfunction "P_P$1") (pintype "passive"))
      (node (ref "R23") (pin "1") (pinfunction "1_1") (pintype "passive"))
    )
    (net (code "26") (name "LED_1") (class "Default")
      (node (ref "SV4") (pin "5") (pinfunction "5_5") (pintype "passive"))
    )
    (net (code "27") (name "LED_2") (class "Default")
      (node (ref "SV4") (pin "3") (pinfunction "3_3") (pintype "passive"))
    )
    (net (code "28") (name "LED_GELB") (class "Default")
      (node (ref "R4") (pin "2") (pinfunction "2_2") (pintype "passive"))
      (node (ref "SV2") (pin "5") (pinfunction "5_5") (pintype "passive"))
    )
    (net (code "29") (name "LED_GRUEN") (class "Default")
      (node (ref "R12") (pin "2") (pinfunction "2_2") (pintype "passive"))
      (node (ref "SV2") (pin "7") (pinfunction "7_7") (pintype "passive"))
    )
    (net (code "30") (name "LED_KICK") (class "Default")
      (node (ref "R24") (pin "2") (pinfunction "2_2") (pintype "passive"))
      (node (ref "SV4") (pin "7") (pinfunction "7_7") (pintype "passive"))
    )
    (net (code "31") (name "LED_ROT") (class "Default")
      (node (ref "R7") (pin "2") (pinfunction "2_2") (pintype "passive"))
      (node (ref "SV2") (pin "3") (pinfunction "3_3") (pintype "passive"))
    )
    (net (code "32") (name "MISO") (class "Default")
      (node (ref "ISP") (pin "1") (pinfunction "1_1") (pintype "passive"))
      (node (ref "U$2") (pin "1") (pinfunction "(MISO_A)PD2_1") (pintype "bidirectional"))
    )
    (net (code "33") (name "MOSI") (class "Default")
      (node (ref "ISP") (pin "4") (pinfunction "4_4") (pintype "passive"))
      (node (ref "JP7") (pin "1") (pinfunction "1_1") (pintype "passive"))
    )
    (net (code "34") (name "MOTION") (class "Default")
      (node (ref "IC4") (pin "1") (pinfunction "O1_1") (pintype "passive"))
      (node (ref "IC4") (pin "5") (pinfunction "O2_5") (pintype "passive"))
      (node (ref "MOT1+") (pin "P$1") (pinfunction "P_P$1") (pintype "passive"))
      (node (ref "MOT2+") (pin "P$1") (pinfunction "P_P$1") (pintype "passive"))
      (node (ref "R15") (pin "1") (pinfunction "1_1") (pintype "passive"))
    )
    (net (code "35") (name "Net-(5V-PadA)") (class "Default")
      (node (ref "5V") (pin "A") (pinfunction "A_A") (pintype "passive"))
      (node (ref "R18") (pin "1") (pinfunction "1_1") (pintype "passive"))
    )
    (net (code "36") (name "Net-(12V-PadA)") (class "Default")
      (node (ref "12V") (pin "A") (pinfunction "A_A") (pintype "passive"))
      (node (ref "R28") (pin "2") (pinfunction "2_2") (pintype "passive"))
    )
    (net (code "37") (name "Net-(GELB-PadA)") (class "Default")
      (node (ref "GELB") (pin "A") (pinfunction "A_A") (pintype "passive"))
      (node (ref "R25") (pin "2") (pinfunction "2_2") (pintype "passive"))
    )
    (net (code "38") (name "Net-(GRÜN-PadA)") (class "Default")
      (node (ref "GRÜN") (pin "A") (pinfunction "A_A") (pintype "passive"))
      (node (ref "R27") (pin "2") (pinfunction "2_2") (pintype "passive"))
    )
    (net (code "39") (name "Net-(IC3-IN)") (class "Default")
      (node (ref "C3") (pin "+") (pinfunction "+_+") (pintype "passive"))
      (node (ref "F2-0.5A") (pin "2") (pinfunction "2_2") (pintype "passive"))
      (node (ref "IC3") (pin "10") (pinfunction "IN_10") (pintype "input"))
    )
    (net (code "40") (name "Net-(IC3-OUT)") (class "Default")
      (node (ref "D3") (pin "C") (pinfunction "C_C") (pintype "passive"))
      (node (ref "IC3") (pin "12") (pinfunction "OUT_12") (pintype "passive"))
      (node (ref "L3") (pin "1") (pinfunction "1_1") (pintype "passive"))
    )
    (net (code "41") (name "Net-(IC4-IN)") (class "Default")
      (node (ref "IC4") (pin "2") (pinfunction "IN_2") (pintype "input"))
      (node (ref "R48") (pin "2") (pinfunction "2_2") (pintype "passive"))
    )
    (net (code "42") (name "Net-(IC7A-C1+)") (class "Default")
      (node (ref "C18") (pin "2") (pinfunction "2_2") (pintype "passive"))
      (node (ref "IC7") (pin "1") (pinfunction "C1+_1") (pintype "bidirectional"))
    )
    (net (code "43") (name "Net-(IC7A-C1-)") (class "Default")
      (node (ref "C18") (pin "1") (pinfunction "1_1") (pintype "passive"))
      (node (ref "IC7") (pin "3") (pinfunction "C1-_3") (pintype "bidirectional"))
    )
    (net (code "44") (name "Net-(IC7A-C2+)") (class "Default")
      (node (ref "C19") (pin "2") (pinfunction "2_2") (pintype "passive"))
      (node (ref "IC7") (pin "4") (pinfunction "C2+_4") (pintype "bidirectional"))
    )
    (net (code "45") (name "Net-(IC7A-C2-)") (class "Default")
      (node (ref "C19") (pin "1") (pinfunction "1_1") (pintype "passive"))
      (node (ref "IC7") (pin "5") (pinfunction "C2-_5") (pintype "bidirectional"))
    )
    (net (code "46") (name "Net-(IC7A-R1IN)") (class "Default")
      (node (ref "IC7") (pin "13") (pinfunction "R1IN_13") (pintype "input"))
      (node (ref "RS232") (pin "3") (pinfunction "3_3") (pintype "passive"))
    )
    (net (code "47") (name "Net-(IC7A-T2OUT)") (class "Default")
      (node (ref "IC7") (pin "7") (pinfunction "T2OUT_7") (pintype "output"))
      (node (ref "RS232") (pin "1") (pinfunction "1_1") (pintype "passive"))
    )
    (net (code "48") (name "Net-(IC7A-V+)") (class "Default")
      (node (ref "C20") (pin "1") (pinfunction "1_1") (pintype "passive"))
      (node (ref "IC7") (pin "2") (pinfunction "V+_2") (pintype "bidirectional"))
    )
    (net (code "49") (name "Net-(IC7A-V-)") (class "Default")
      (node (ref "C21") (pin "1") (pinfunction "1_1") (pintype "passive"))
      (node (ref "IC7") (pin "6") (pinfunction "V-_6") (pintype "bidirectional"))
    )
    (net (code "50") (name "Net-(IC10-PadIN)") (class "Default")
      (node (ref "IC10") (pin "IN") (pinfunction "IN_IN") (pintype "input"))
      (node (ref "R50") (pin "2") (pinfunction "2_2") (pintype "passive"))
    )
    (net (code "51") (name "Net-(IC11-PadIN)") (class "Default")
      (node (ref "IC11") (pin "IN") (pinfunction "IN_IN") (pintype "input"))
      (node (ref "R49") (pin "2") (pinfunction "2_2") (pintype "passive"))
    )
    (net (code "52") (name "Net-(IC12-PadIN)") (class "Default")
      (node (ref "IC12") (pin "IN") (pinfunction "IN_IN") (pintype "input"))
      (node (ref "R47") (pin "2") (pinfunction "2_2") (pintype "passive"))
    )
    (net (code "53") (name "Net-(IC15-PadIN)") (class "Default")
      (node (ref "IC15") (pin "IN") (pinfunction "IN_IN") (pintype "input"))
      (node (ref "R22") (pin "2") (pinfunction "2_2") (pintype "passive"))
    )
    (net (code "54") (name "Net-(JP1-Pad1)") (class "Default")
      (node (ref "JP1") (pin "1") (pinfunction "1_1") (pintype "passive"))
      (node (ref "R6") (pin "2") (pinfunction "2_2") (pintype "passive"))
    )
    (net (code "55") (name "Net-(KICK-PadA)") (class "Default")
      (node (ref "KICK") (pin "A") (pinfunction "A_A") (pintype "passive"))
      (node (ref "R29") (pin "2") (pinfunction "2_2") (pintype "passive"))
    )
    (net (code "56") (name "Net-(R26-Pad2)") (class "Default")
      (node (ref "R26") (pin "2") (pinfunction "2_2") (pintype "passive"))
      (node (ref "ROT") (pin "A") (pinfunction "A_A") (pintype "passive"))
    )
    (net (code "57") (name "Net-(R36-Pad1)") (class "Default")
      (node (ref "R36") (pin "1") (pinfunction "1_1") (pintype "passive"))
      (node (ref "R44") (pin "2") (pinfunction "2_2") (pintype "passive"))
    )
    (net (code "58") (name "Net-(R38-Pad1)") (class "Default")
      (node (ref "R38") (pin "1") (pinfunction "1_1") (pintype "passive"))
      (node (ref "R42") (pin "2") (pinfunction "2_2") (pintype "passive"))
    )
    (net (code "59") (name "Net-(R40-Pad1)") (class "Default")
      (node (ref "R40") (pin "1") (pinfunction "1_1") (pintype "passive"))
      (node (ref "R43") (pin "2") (pinfunction "2_2") (pintype "passive"))
    )
    (net (code "60") (name "Net-(RJ_1-PadP$1)") (class "Default")
      (node (ref "RJ_1") (pin "P$1") (pinfunction "P$1_P$1") (pintype "bidirectional"))
      (node (ref "RJ_2") (pin "P$1") (pinfunction "P$1_P$1") (pintype "bidirectional"))
      (node (ref "SJ2") (pin "2") (pinfunction "2_2") (pintype "passive"))
    )
    (net (code "61") (name "Net-(T1-B)") (class "Default")
      (node (ref "R5") (pin "2") (pinfunction "2_2") (pintype "passive"))
      (node (ref "T1") (pin "1") (pinfunction "B_1") (pintype "passive"))
    )
    (net (code "62") (name "Net-(T1-C)") (class "Default")
      (node (ref "T1") (pin "3") (pinfunction "C_3") (pintype "passive"))
      (node (ref "TDB-05") (pin "-") (pinfunction "2_-") (pintype "passive"))
    )
    (net (code "63") (name "Net-(T2-B)") (class "Default")
      (node (ref "R23") (pin "2") (pinfunction "2_2") (pintype "passive"))
      (node (ref "T2") (pin "1") (pinfunction "B_1") (pintype "passive"))
    )
    (net (code "64") (name "Net-(T5-B)") (class "Default")
      (node (ref "R16") (pin "2") (pinfunction "2_2") (pintype "passive"))
      (node (ref "T5") (pin "1") (pinfunction "B_1") (pintype "passive"))
    )
    (net (code "65") (name "Net-(T6-B)") (class "Default")
      (node (ref "R17") (pin "2") (pinfunction "2_2") (pintype "passive"))
      (node (ref "T6") (pin "1") (pinfunction "B_1") (pintype "passive"))
    )
    (net (code "66") (name "Net-(T7-B)") (class "Default")
      (node (ref "R15") (pin "2") (pinfunction "2_2") (pintype "passive"))
      (node (ref "T7") (pin "1") (pinfunction "B_1") (pintype "passive"))
    )
    (net (code "67") (name "Net-(U$1-RS)") (class "Default")
      (node (ref "R31") (pin "2") (pinfunction "2_2") (pintype "passive"))
      (node (ref "U$1") (pin "8") (pinfunction "RS_8") (pintype "input"))
    )
    (net (code "68") (name "Net-(U$2-(MOSI_A{slash}TXD)PD3)") (class "Default")
      (node (ref "JP7") (pin "2") (pinfunction "2_2") (pintype "passive"))
      (node (ref "U$2") (pin "2") (pinfunction "(MOSI_A/TXD)PD3_2") (pintype "bidirectional"))
    )
    (net (code "69") (name "Net-(U$2-(RXD)PD4)") (class "Default")
      (node (ref "JP6") (pin "2") (pinfunction "2_2") (pintype "passive"))
      (node (ref "U$2") (pin "12") (pinfunction "(RXD)PD4_12") (pintype "bidirectional"))
    )
    (net (code "70") (name "Net-(U$2-AREF)") (class "Default")
      (node (ref "C14") (pin "2") (pinfunction "2_2") (pintype "passive"))
      (node (ref "U$2") (pin "21") (pinfunction "AREF_21") (pintype "bidirectional"))
    )
    (net (code "71") (name "Net-(U$2-AVCC)") (class "Default")
      (node (ref "C16") (pin "1") (pinfunction "1_1") (pintype "passive"))
      (node (ref "L1") (pin "1") (pinfunction "1_1") (pintype "passive"))
      (node (ref "U$2") (pin "19") (pinfunction "AVCC_19") (pintype "bidirectional"))
    )
    (net (code "72") (name "Net-(U$2-PE1(XTAL1))") (class "Default")
      (node (ref "C11") (pin "2") (pinfunction "2_2") (pintype "passive"))
      (node (ref "Q1") (pin "1") (pinfunction "1_1") (pintype "passive"))
      (node (ref "U$2") (pin "10") (pinfunction "PE1(XTAL1)_10") (pintype "bidirectional"))
    )
    (net (code "73") (name "Net-(U$2-PE2(XTAL2))") (class "Default")
      (node (ref "C10") (pin "2") (pinfunction "2_2") (pintype "passive"))
      (node (ref "Q1") (pin "2") (pinfunction "2_2") (pintype "passive"))
      (node (ref "U$2") (pin "11") (pinfunction "PE2(XTAL2)_11") (pintype "bidirectional"))
    )
    (net (code "74") (name "Net-(VR6-A)") (class "Default")
      (node (ref "JP5") (pin "2") (pinfunction "2_2") (pintype "passive"))
      (node (ref "R22") (pin "1") (pinfunction "1_1") (pintype "passive"))
      (node (ref "VR6") (pin "3") (pinfunction "A_3") (pintype "passive"))
    )
    (net (code "75") (name "Net-(VR6-C)") (class "Default")
      (node (ref "R50") (pin "1") (pinfunction "1_1") (pintype "passive"))
      (node (ref "VR6") (pin "1") (pinfunction "C_1") (pintype "passive"))
    )
    (net (code "76") (name "Net-(VR7-A)") (class "Default")
      (node (ref "JP2") (pin "2") (pinfunction "2_2") (pintype "passive"))
      (node (ref "VR7") (pin "3") (pinfunction "A_3") (pintype "passive"))
    )
    (net (code "77") (name "Net-(VR7-C)") (class "Default")
      (node (ref "R49") (pin "1") (pinfunction "1_1") (pintype "passive"))
      (node (ref "VR7") (pin "1") (pinfunction "C_1") (pintype "passive"))
    )
    (net (code "78") (name "Net-(VR7-R)") (class "Default")
      (node (ref "R36") (pin "2") (pinfunction "2_2") (pintype "passive"))
      (node (ref "R37") (pin "1") (pinfunction "1_1") (pintype "passive"))
      (node (ref "VR7") (pin "2") (pinfunction "R_2") (pintype "passive"))
    )
    (net (code "79") (name "Net-(VR8-A)") (class "Default")
      (node (ref "JP3") (pin "2") (pinfunction "2_2") (pintype "passive"))
      (node (ref "VR8") (pin "3") (pinfunction "A_3") (pintype "passive"))
    )
    (net (code "80") (name "Net-(VR8-C)") (class "Default")
      (node (ref "R47") (pin "1") (pinfunction "1_1") (pintype "passive"))
      (node (ref "VR8") (pin "1") (pinfunction "C_1") (pintype "passive"))
    )
    (net (code "81") (name "Net-(VR8-R)") (class "Default")
      (node (ref "R38") (pin "2") (pinfunction "2_2") (pintype "passive"))
      (node (ref "R39") (pin "1") (pinfunction "1_1") (pintype "passive"))
      (node (ref "VR8") (pin "2") (pinfunction "R_2") (pintype "passive"))
    )
    (net (code "82") (name "Net-(VR9-A)") (class "Default")
      (node (ref "JP4") (pin "2") (pinfunction "2_2") (pintype "passive"))
      (node (ref "VR9") (pin "3") (pinfunction "A_3") (pintype "passive"))
    )
    (net (code "83") (name "Net-(VR9-C)") (class "Default")
      (node (ref "R48") (pin "1") (pinfunction "1_1") (pintype "passive"))
      (node (ref "VR9") (pin "1") (pinfunction "C_1") (pintype "passive"))
    )
    (net (code "84") (name "Net-(VR9-R)") (class "Default")
      (node (ref "R40") (pin "2") (pinfunction "2_2") (pintype "passive"))
      (node (ref "R41") (pin "1") (pinfunction "1_1") (pintype "passive"))
      (node (ref "VR9") (pin "2") (pinfunction "R_2") (pintype "passive"))
    )
    (net (code "85") (name "Net-(VR10-C)") (class "Default")
      (node (ref "R30") (pin "2") (pinfunction "2_2") (pintype "passive"))
      (node (ref "R35") (pin "1") (pinfunction "1_1") (pintype "passive"))
      (node (ref "VR10") (pin "1") (pinfunction "C_1") (pintype "passive"))
      (node (ref "VR6") (pin "2") (pinfunction "R_2") (pintype "passive"))
    )
    (net (code "86") (name "Net-(VR10-R)") (class "Default")
      (node (ref "R45") (pin "1") (pinfunction "1_1") (pintype "passive"))
      (node (ref "R46") (pin "2") (pinfunction "2_2") (pintype "passive"))
      (node (ref "VR10") (pin "2") (pinfunction "R_2") (pintype "passive"))
    )
    (net (code "87") (name "RESET") (class "Default")
      (node (ref "ISP") (pin "5") (pinfunction "5_5") (pintype "passive"))
    )
    (net (code "88") (name "RST") (class "Default")
      (node (ref "C13") (pin "2") (pinfunction "2_2") (pintype "passive"))
      (node (ref "R1") (pin "1") (pinfunction "1_1") (pintype "passive"))
      (node (ref "U$2") (pin "31") (pinfunction "PE0(RESET)_31") (pintype "input"))
    )
    (net (code "89") (name "RXCAN") (class "Default")
      (node (ref "U$1") (pin "4") (pinfunction "RXD_4") (pintype "output"))
      (node (ref "U$2") (pin "7") (pinfunction "(RXCAN)PC3_7") (pintype "bidirectional"))
    )
    (net (code "90") (name "RXD") (class "Default")
      (node (ref "IC7") (pin "12") (pinfunction "R1OUT_12") (pintype "output"))
      (node (ref "JP6") (pin "3") (pinfunction "3_3") (pintype "passive"))
    )
    (net (code "91") (name "SCK") (class "Default")
      (node (ref "ISP") (pin "3") (pinfunction "3_3") (pintype "passive"))
      (node (ref "JP6") (pin "1") (pinfunction "1_1") (pintype "passive"))
    )
    (net (code "92") (name "SPEAKER") (class "Default")
      (node (ref "R5") (pin "1") (pinfunction "1_1") (pintype "passive"))
      (node (ref "U$2") (pin "29") (pinfunction "PD0_29") (pintype "bidirectional"))
    )
    (net (code "93") (name "SW_1") (class "Default")
      (node (ref "SV4") (pin "6") (pinfunction "6_6") (pintype "passive"))
      (node (ref "U$2") (pin "3") (pinfunction "PC1_3") (pintype "bidirectional"))
    )
    (net (code "94") (name "SW_2") (class "Default")
      (node (ref "SV4") (pin "4") (pinfunction "4_4") (pintype "passive"))
    )
    (net (code "95") (name "SW_12V") (class "Default")
      (node (ref "JP5") (pin "1") (pinfunction "1_1") (pintype "passive"))
      (node (ref "SV2") (pin "4") (pinfunction "4_4") (pintype "passive"))
    )
    (net (code "96") (name "SW_AKT") (class "Default")
      (node (ref "JP2") (pin "1") (pinfunction "1_1") (pintype "passive"))
      (node (ref "JP9") (pin "2") (pinfunction "2_2") (pintype "passive"))
      (node (ref "SV2") (pin "6") (pinfunction "6_6") (pintype "passive"))
      (node (ref "U$2") (pin "8") (pinfunction "PB0_8") (pintype "bidirectional"))
    )
    (net (code "97") (name "SW_KICK") (class "Default")
      (node (ref "JP3") (pin "1") (pinfunction "1_1") (pintype "passive"))
      (node (ref "JP9") (pin "1") (pinfunction "1_1") (pintype "passive"))
      (node (ref "SV4") (pin "8") (pinfunction "8_8") (pintype "passive"))
      (node (ref "U$2") (pin "25") (pinfunction "PC7_25") (pintype "bidirectional"))
    )
    (net (code "98") (name "SW_MOT") (class "Default")
      (node (ref "JP4") (pin "1") (pinfunction "1_1") (pintype "passive"))
      (node (ref "SV2") (pin "8") (pinfunction "8_8") (pintype "passive"))
      (node (ref "U$2") (pin "9") (pinfunction "PB1_9") (pintype "bidirectional"))
    )
    (net (code "99") (name "TXCAN") (class "Default")
      (node (ref "U$1") (pin "1") (pinfunction "TXD_1") (pintype "input"))
      (node (ref "U$2") (pin "6") (pinfunction "(TXCAN)PC2_6") (pintype "bidirectional"))
    )
    (net (code "100") (name "TXD") (class "Default")
      (node (ref "IC7") (pin "10") (pinfunction "T2IN_10") (pintype "input"))
      (node (ref "JP7") (pin "3") (pinfunction "3_3") (pintype "passive"))
    )
    (net (code "101") (name "unconnected-(IC7A-R2OUT-Pad9)") (class "Default")
      (node (ref "IC7") (pin "9") (pinfunction "R2OUT_9") (pintype "output"))
    )
    (net (code "102") (name "unconnected-(IC7A-T1OUT-Pad14)") (class "Default")
      (node (ref "IC7") (pin "14") (pinfunction "T1OUT_14") (pintype "output"))
    )
    (net (code "103") (name "unconnected-(RS232-Pad2)") (class "Default")
      (node (ref "RS232") (pin "2") (pinfunction "2_2") (pintype "passive"))
    )
    (net (code "104") (name "unconnected-(RS232-Pad4)") (class "Default")
      (node (ref "RS232") (pin "4") (pinfunction "4_4") (pintype "passive"))
    )
    (net (code "105") (name "unconnected-(RS232-Pad6)") (class "Default")
      (node (ref "RS232") (pin "6") (pinfunction "6_6") (pintype "passive"))
    )
    (net (code "106") (name "unconnected-(U$1-VREF-Pad5)") (class "Default")
      (node (ref "U$1") (pin "5") (pinfunction "VREF_5") (pintype "output"))
    )
    (net (code "107") (name "unconnected-(U$2-PD7-Pad15)") (class "Default")
      (node (ref "U$2") (pin "15") (pinfunction "PD7_15") (pintype "bidirectional"))
    )
  )
)
